# ATTAMI.net
KiCad netlist of a schematic drawn in EAGLE
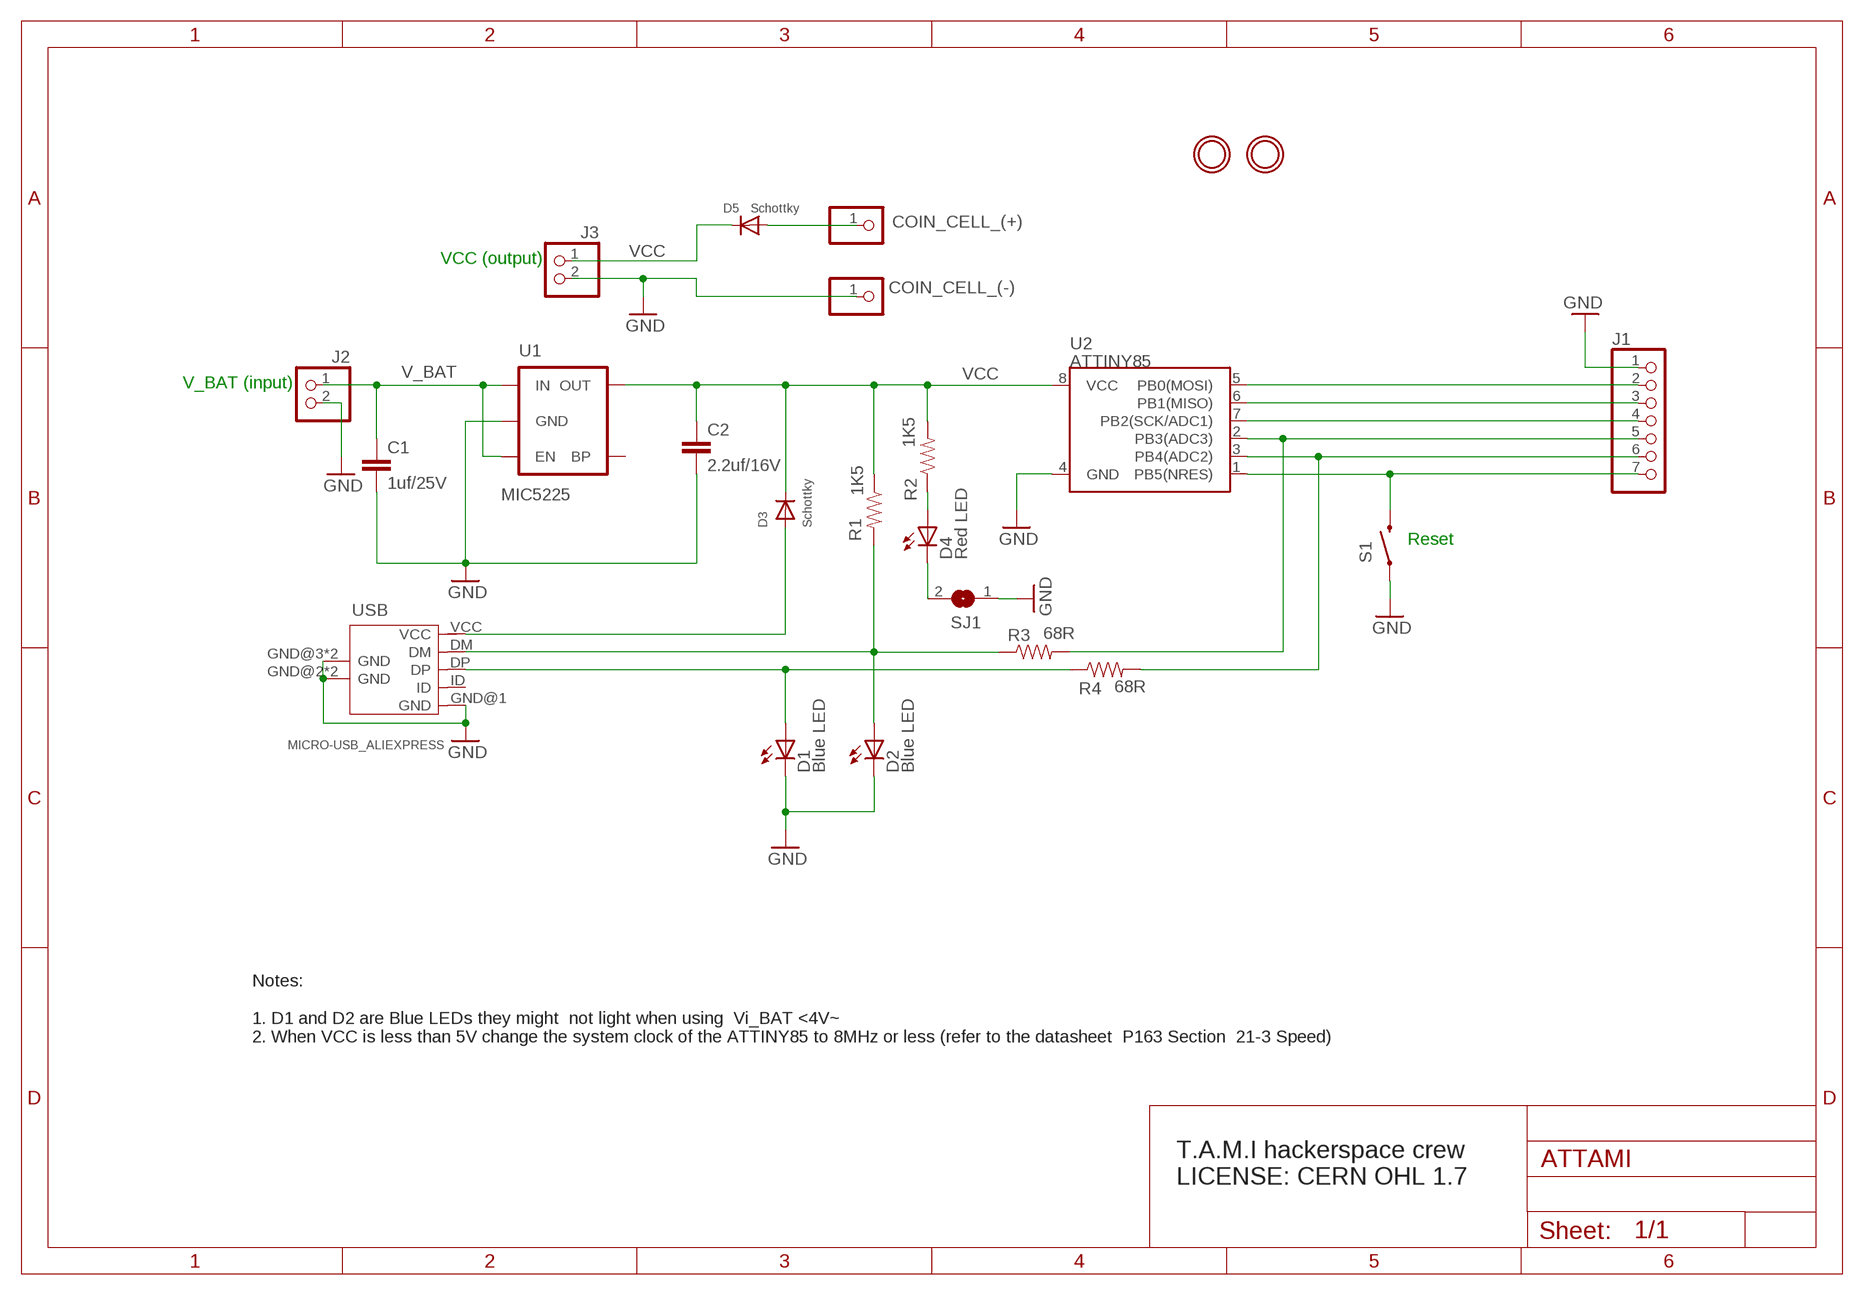
[diagram p0: schematic, sheet 1]

(export (version "E")
  (design (tool "Eeschema 10.0.6"))
  (components
    (comp (ref "C1")
      (value "1uf/25V")
      (footprint "eagle-import:0805")
      (libsource (lib "eagle-import") (part "CAP0805"))
    )
    (comp (ref "C2")
      (value "2.2uf/16V")
      (footprint "eagle-import:0805")
      (libsource (lib "eagle-import") (part "CAP0805"))
    )
    (comp (ref "COIN_CELL_(+)")
      (value "PINHD-1X1CB")
      (footprint "eagle-import:1X01-CLEANBIG")
      (libsource (lib "eagle-import") (part "PINHD-1X1CB"))
    )
    (comp (ref "COIN_CELL_(-)")
      (value "PINHD-1X1CB")
      (footprint "eagle-import:1X01-CLEANBIG")
      (libsource (lib "eagle-import") (part "PINHD-1X1CB"))
    )
    (comp (ref "D1")
      (value "Blue LED")
      (footprint "eagle-import:LED-805")
      (libsource (lib "eagle-import") (part "LED-0805"))
    )
    (comp (ref "D2")
      (value "Blue LED")
      (footprint "eagle-import:LED-805")
      (libsource (lib "eagle-import") (part "LED-0805"))
    )
    (comp (ref "D3")
      (value "Schottky")
      (footprint "eagle-import:SOD-323")
      (libsource (lib "eagle-import") (part "DIODESOD-323"))
    )
    (comp (ref "D4")
      (value "Red LED")
      (footprint "eagle-import:LED-805")
      (libsource (lib "eagle-import") (part "LED-0805"))
    )
    (comp (ref "D5")
      (value "Schottky")
      (footprint "eagle-import:SOD-323")
      (libsource (lib "eagle-import") (part "DIODESOD-323"))
    )
    (comp (ref "J1")
      (value "HEADER-1X7ROUND")
      (footprint "eagle-import:1X07_ROUND")
      (libsource (lib "eagle-import") (part "HEADER-1X7ROUND"))
    )
    (comp (ref "J2")
      (value "HEADER-1X2ROUND")
      (footprint "eagle-import:1X02_ROUND")
      (libsource (lib "eagle-import") (part "HEADER-1X2ROUND"))
    )
    (comp (ref "J3")
      (value "HEADER-1X2ROUND")
      (footprint "eagle-import:1X02_ROUND")
      (libsource (lib "eagle-import") (part "HEADER-1X2ROUND"))
    )
    (comp (ref "R1")
      (value "1K5")
      (footprint "eagle-import:0805")
      (libsource (lib "eagle-import") (part "RESISTOR0805-RES"))
    )
    (comp (ref "R2")
      (value "1K5")
      (footprint "eagle-import:0805")
      (libsource (lib "eagle-import") (part "RESISTOR0805-RES"))
    )
    (comp (ref "R3")
      (value "68R")
      (footprint "eagle-import:0805")
      (libsource (lib "eagle-import") (part "RESISTOR0805-RES"))
    )
    (comp (ref "R4")
      (value "68R")
      (footprint "eagle-import:0805")
      (libsource (lib "eagle-import") (part "RESISTOR0805-RES"))
    )
    (comp (ref "S1")
      (value "SWITCH-MOMENTARY-2-SMD-1101NE")
      (footprint "eagle-import:TACTILE-SWITCH-1101NE")
      (libsource (lib "eagle-import") (part "SWITCH-MOMENTARY-2-SMD-1101NE"))
    )
    (comp (ref "SJ1")
      (value "SOLDERJUMPERCLOSED")
      (footprint "eagle-import:SOLDERJUMPER_CLOSEDWIRE")
      (libsource (lib "eagle-import") (part "SOLDERJUMPERCLOSED"))
    )
    (comp (ref "U$1")
      (value "MOUNTINGHOLE2.0")
      (footprint "eagle-import:MOUNTINGHOLE_2.0_PLATED")
      (libsource (lib "eagle-import") (part "MOUNTINGHOLE2.0"))
    )
    (comp (ref "U$2")
      (value "MOUNTINGHOLE2.0")
      (footprint "eagle-import:MOUNTINGHOLE_2.0_PLATED")
      (libsource (lib "eagle-import") (part "MOUNTINGHOLE2.0"))
    )
    (comp (ref "U1")
      (value "MIC5225")
      (footprint "eagle-import:SOT23-5")
      (libsource (lib "eagle-import") (part "V_REG_LDOSMD"))
    )
    (comp (ref "U2")
      (value "ATTINY85")
      (footprint "eagle-import:SO08-EIAJ")
      (libsource (lib "eagle-import") (part "ATTINY45"))
    )
    (comp (ref "USB")
      (value "MICRO-USB_ALIEXPRESS")
      (footprint "eagle-import:USB-MICRO-ALIEXPRESS")
      (libsource (lib "eagle-import") (part "MICRO-USB_ALIEXPRESS"))
    )
  )
  (nets
    (net (code "1") (name "/VCC") (class "Default")
      (node (ref "C2") (pin "1") (pinfunction "1_1") (pintype "passive"))
      (node (ref "D3") (pin "CQ") (pinfunction "C_CQ") (pintype "passive"))
      (node (ref "D5") (pin "CQ") (pinfunction "C_CQ") (pintype "passive"))
      (node (ref "J3") (pin "1") (pinfunction "1_1") (pintype "passive"))
      (node (ref "R1") (pin "1") (pinfunction "1_1") (pintype "passive"))
      (node (ref "R2") (pin "2") (pinfunction "2_2") (pintype "passive"))
      (node (ref "U1") (pin "5") (pinfunction "OUT_5") (pintype "passive"))
      (node (ref "U2") (pin "8") (pinfunction "VCC_8") (pintype "bidirectional"))
    )
    (net (code "2") (name "/V_BAT") (class "Default")
      (node (ref "C1") (pin "1") (pinfunction "1_1") (pintype "passive"))
      (node (ref "J2") (pin "1") (pinfunction "1_1") (pintype "passive"))
      (node (ref "U1") (pin "1") (pinfunction "IN_1") (pintype "input"))
      (node (ref "U1") (pin "3") (pinfunction "EN_3") (pintype "input"))
    )
    (net (code "3") (name "GND") (class "Default")
      (node (ref "C1") (pin "2") (pinfunction "2_2") (pintype "passive"))
      (node (ref "C2") (pin "2") (pinfunction "2_2") (pintype "passive"))
      (node (ref "COIN_CELL_(-)") (pin "1") (pinfunction "1_1") (pintype "passive"))
      (node (ref "D1") (pin "C") (pinfunction "C_C") (pintype "passive"))
      (node (ref "D2") (pin "C") (pinfunction "C_C") (pintype "passive"))
      (node (ref "J1") (pin "1") (pinfunction "1_1") (pintype "passive"))
      (node (ref "J2") (pin "2") (pinfunction "2_2") (pintype "passive"))
      (node (ref "J3") (pin "2") (pinfunction "2_2") (pintype "passive"))
      (node (ref "S1") (pin "P$1") (pinfunction "1_P$1") (pintype "passive"))
      (node (ref "SJ1") (pin "1") (pinfunction "1_1") (pintype "passive"))
      (node (ref "U1") (pin "2") (pinfunction "GND_2") (pintype "input"))
      (node (ref "U2") (pin "4") (pinfunction "GND_4") (pintype "bidirectional"))
      (node (ref "USB") (pin "GND@1") (pinfunction "GND_GND@1") (pintype "bidirectional"))
      (node (ref "USB") (pin "GND@2") (pinfunction "GND_GND@2") (pintype "bidirectional"))
      (node (ref "USB") (pin "GND@3") (pinfunction "GND_GND@3") (pintype "bidirectional"))
      (node (ref "USB") (pin "P$10") (pinfunction "GND_P$10") (pintype "bidirectional"))
      (node (ref "USB") (pin "P$9") (pinfunction "GND_P$9") (pintype "bidirectional"))
    )
    (net (code "4") (name "Net-(D1-PadA)") (class "Default")
      (node (ref "D1") (pin "A") (pinfunction "A_A") (pintype "passive"))
      (node (ref "R4") (pin "1") (pinfunction "1_1") (pintype "passive"))
      (node (ref "USB") (pin "DP") (pinfunction "DP_DP") (pintype "bidirectional"))
    )
    (net (code "5") (name "Net-(D2-PadA)") (class "Default")
      (node (ref "D2") (pin "A") (pinfunction "A_A") (pintype "passive"))
      (node (ref "R1") (pin "2") (pinfunction "2_2") (pintype "passive"))
      (node (ref "R3") (pin "1") (pinfunction "1_1") (pintype "passive"))
      (node (ref "USB") (pin "DM") (pinfunction "DM_DM") (pintype "bidirectional"))
    )
    (net (code "6") (name "Net-(D3-A)") (class "Default")
      (node (ref "D3") (pin "AQ") (pinfunction "A_AQ") (pintype "passive"))
      (node (ref "USB") (pin "VCC") (pinfunction "VCC_VCC") (pintype "bidirectional"))
    )
    (net (code "7") (name "Net-(D4-PadA)") (class "Default")
      (node (ref "D4") (pin "A") (pinfunction "A_A") (pintype "passive"))
      (node (ref "R2") (pin "1") (pinfunction "1_1") (pintype "passive"))
    )
    (net (code "8") (name "Net-(D4-PadC)") (class "Default")
      (node (ref "D4") (pin "C") (pinfunction "C_C") (pintype "passive"))
      (node (ref "SJ1") (pin "2") (pinfunction "2_2") (pintype "passive"))
    )
    (net (code "9") (name "Net-(D5-A)") (class "Default")
      (node (ref "COIN_CELL_(+)") (pin "1") (pinfunction "1_1") (pintype "passive"))
      (node (ref "D5") (pin "AQ") (pinfunction "A_AQ") (pintype "passive"))
    )
    (net (code "10") (name "Net-(S1-2)") (class "Default")
      (node (ref "J1") (pin "7") (pinfunction "7_7") (pintype "passive"))
      (node (ref "S1") (pin "P$2") (pinfunction "2_P$2") (pintype "passive"))
      (node (ref "U2") (pin "1") (pinfunction "PB5(NRES)_1") (pintype "bidirectional"))
    )
    (net (code "11") (name "Net-(U2-PB0(MOSI))") (class "Default")
      (node (ref "J1") (pin "2") (pinfunction "2_2") (pintype "passive"))
      (node (ref "U2") (pin "5") (pinfunction "PB0(MOSI)_5") (pintype "bidirectional"))
    )
    (net (code "12") (name "Net-(U2-PB1(MISO))") (class "Default")
      (node (ref "J1") (pin "3") (pinfunction "3_3") (pintype "passive"))
      (node (ref "U2") (pin "6") (pinfunction "PB1(MISO)_6") (pintype "bidirectional"))
    )
    (net (code "13") (name "Net-(U2-PB2(SCK{slash}ADC1))") (class "Default")
      (node (ref "J1") (pin "4") (pinfunction "4_4") (pintype "passive"))
      (node (ref "U2") (pin "7") (pinfunction "PB2(SCK/ADC1)_7") (pintype "bidirectional"))
    )
    (net (code "14") (name "Net-(U2-PB3(ADC3))") (class "Default")
      (node (ref "J1") (pin "5") (pinfunction "5_5") (pintype "passive"))
      (node (ref "R3") (pin "2") (pinfunction "2_2") (pintype "passive"))
      (node (ref "U2") (pin "2") (pinfunction "PB3(ADC3)_2") (pintype "bidirectional"))
    )
    (net (code "15") (name "Net-(U2-PB4(ADC2))") (class "Default")
      (node (ref "J1") (pin "6") (pinfunction "6_6") (pintype "passive"))
      (node (ref "R4") (pin "2") (pinfunction "2_2") (pintype "passive"))
      (node (ref "U2") (pin "3") (pinfunction "PB4(ADC2)_3") (pintype "bidirectional"))
    )
    (net (code "16") (name "unconnected-(U1-BP-Pad4)") (class "Default")
      (node (ref "U1") (pin "4") (pinfunction "BP_4") (pintype "input"))
    )
    (net (code "17") (name "unconnected-(USB-PadID)") (class "Default")
      (node (ref "USB") (pin "ID") (pinfunction "ID_ID") (pintype "bidirectional"))
    )
  )
)
